# SCH_fateh_reverse_voltage_protection_cir.net
KiCad netlist of a schematic drawn in EasyEDA
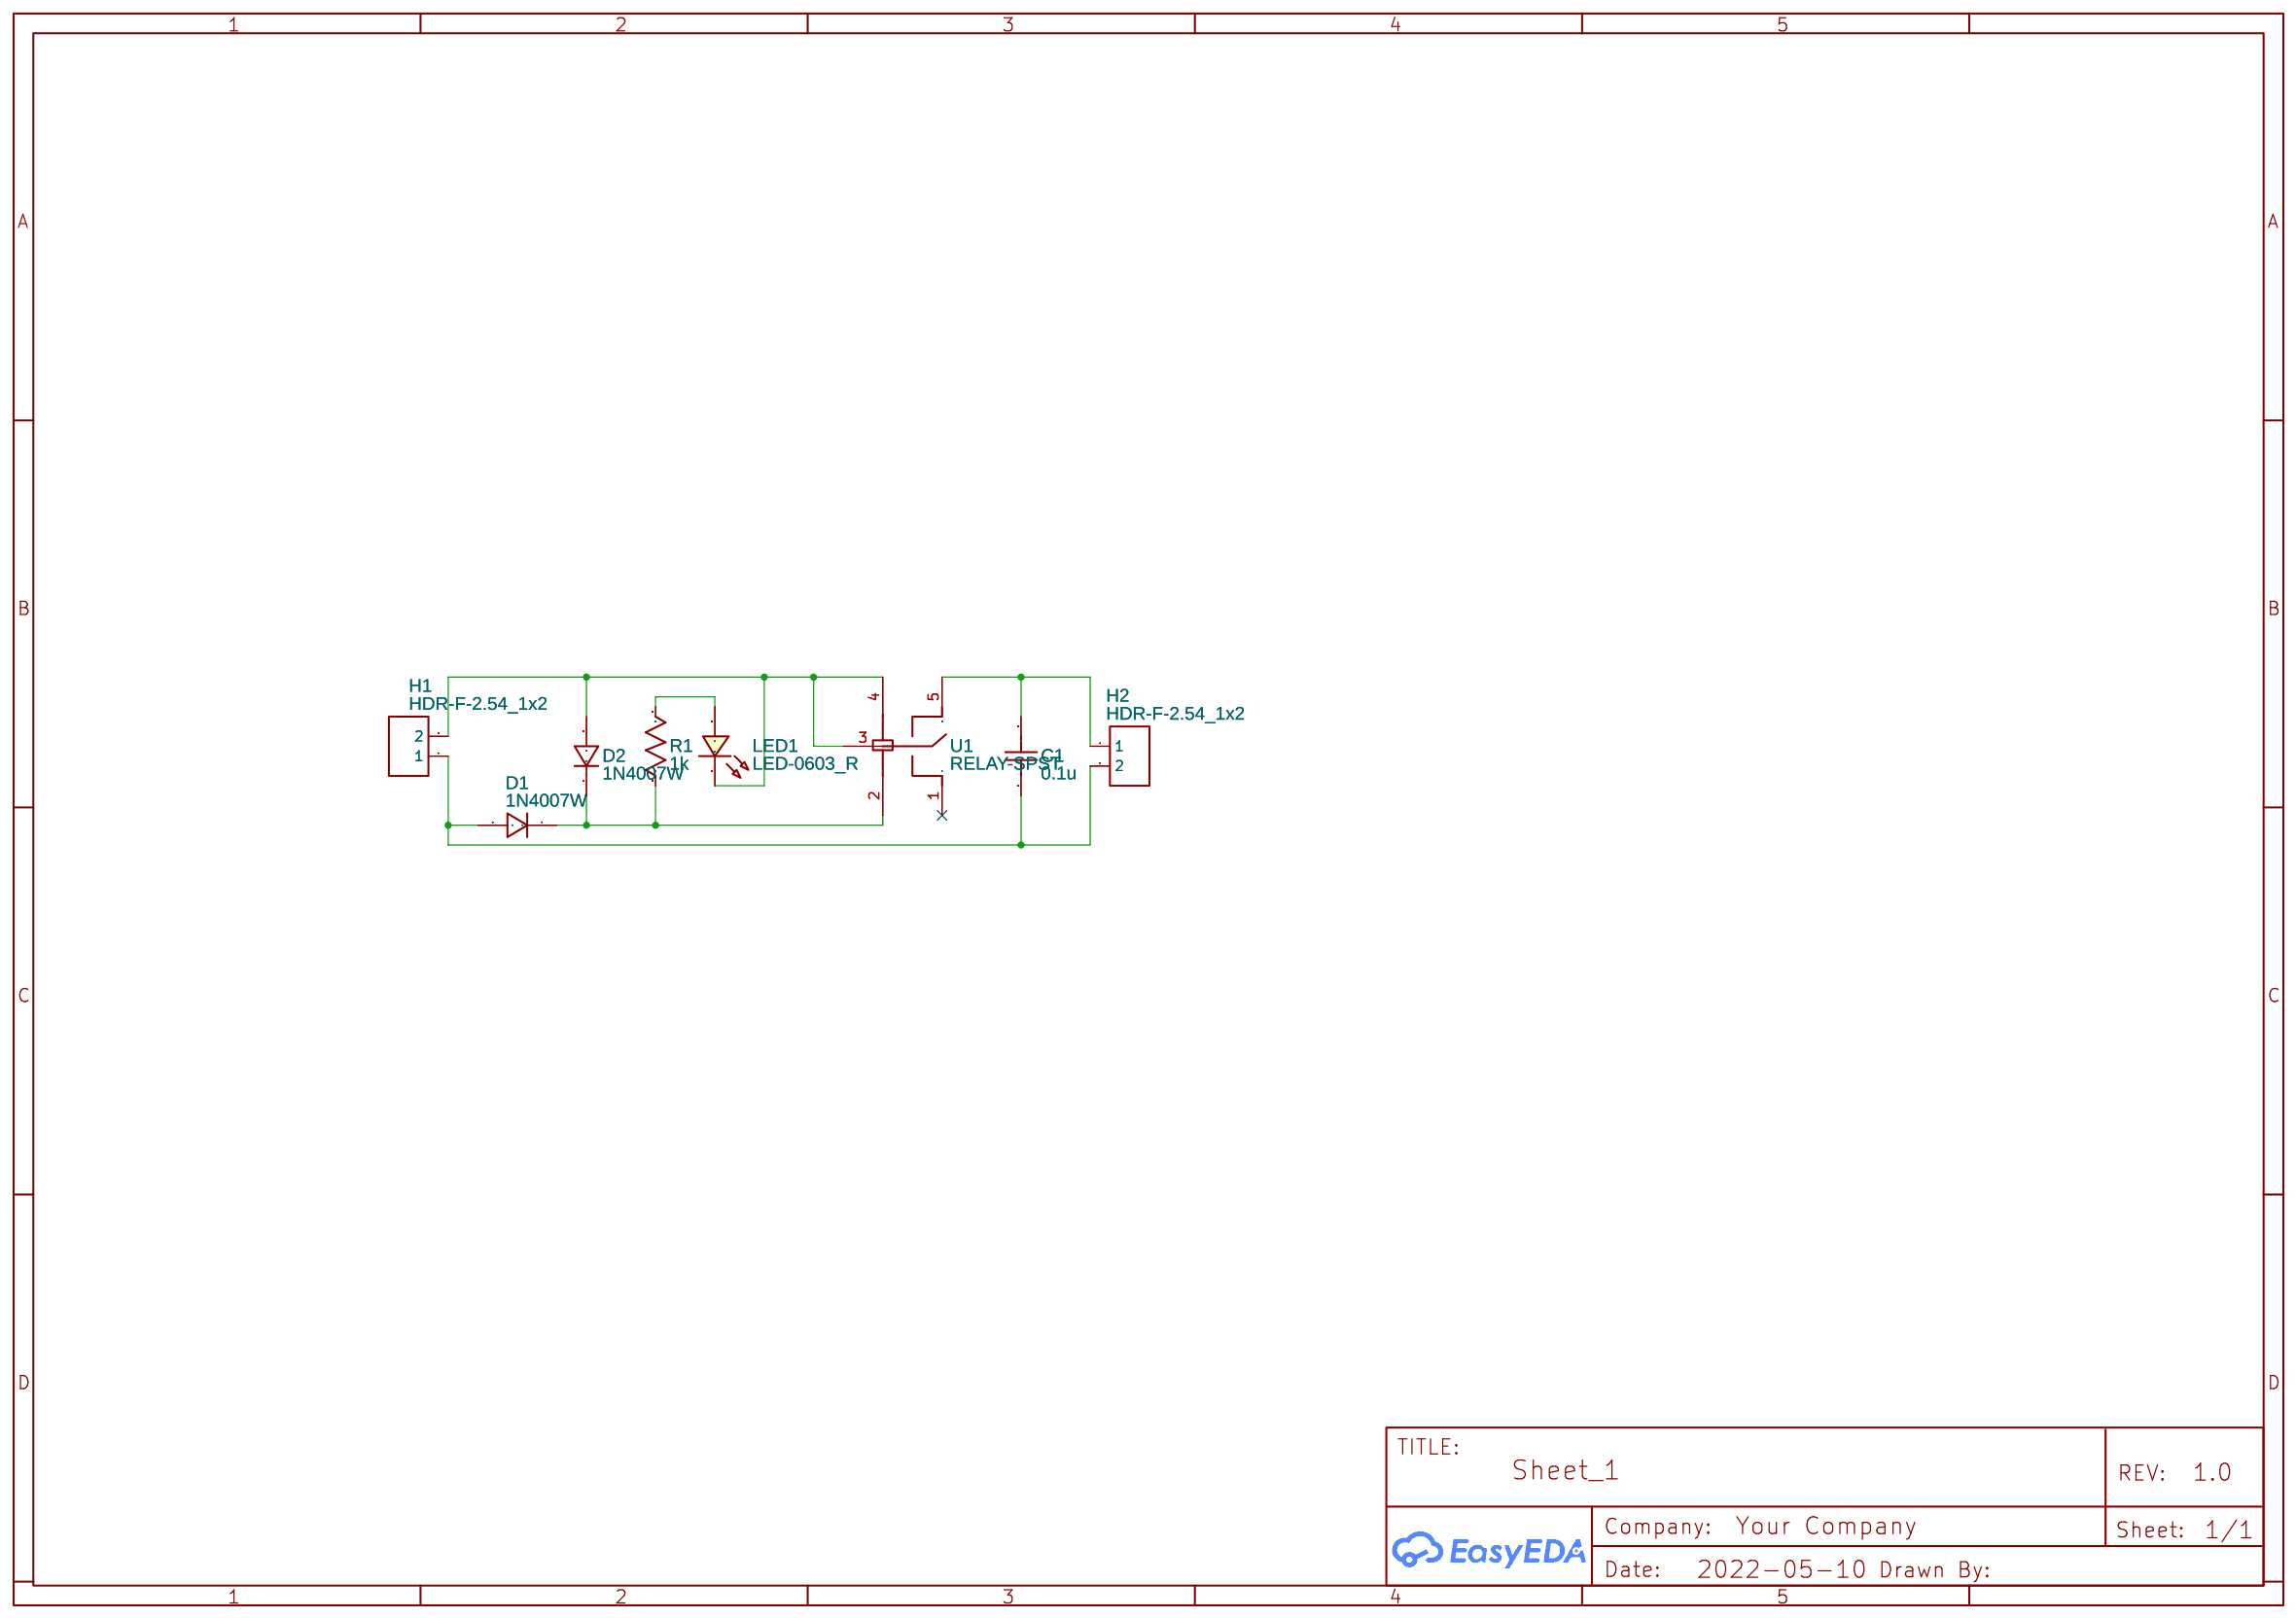
[diagram p0: schematic sheet]

(export (version "E")
  (design (tool "Eeschema 10.0.6"))
  (components
    (comp (ref "C1") (value "0.1u") (libsource (lib "") (part "C_0603_US")))
    (comp (ref "D1")
      (value "1N4007W")
      (fields (field (name "BOM_Supplier Part") "C328592"))
      (libsource (lib "") (part "1N4007W_1"))
    )
    (comp (ref "D2")
      (value "1N4007W")
      (fields (field (name "BOM_Supplier Part") "C328592"))
      (libsource (lib "") (part "1N4007W"))
    )
    (comp (ref "H1")
      (value "HDR-F-2.54_1x2")
      (fields (field (name "BOM_Supplier Part") "C49661"))
      (libsource (lib "") (part "HDR-F-2.54_1x2_1"))
    )
    (comp (ref "H2")
      (value "HDR-F-2.54_1x2")
      (fields (field (name "BOM_Supplier Part") "C49661"))
      (libsource (lib "") (part "HDR-F-2.54_1x2"))
    )
    (comp (ref "LED1")
      (value "LED-0603_R")
      (fields
        (field (name "BOM_Manufacturer Part") "19-217/R6C-AL1M2VY/3T")
        (field (name "BOM_Supplier Part") "C72044")
      )
      (libsource (lib "") (part "LED-0603_R"))
    )
    (comp (ref "R1") (value "1k") (libsource (lib "") (part "R_AXIAL-0.3_US")))
    (comp (ref "U1")
      (value "RELAY-SPST")
      (fields
        (field (name "BOM_Manufacturer Part") "Relay-SPST")
        (field (name "BOM_Supplier Part") "C2941249")
      )
      (libsource (lib "") (part "RELAY-SPST"))
    )
  )
  (nets
    (net (code "1") (name "Net-(C1-Pad1)") (class "Default")
      (node (ref "C1") (pin "1") (pinfunction "1_1") (pintype "unspecified"))
      (node (ref "D1") (pin "2") (pinfunction "2_2") (pintype "unspecified"))
      (node (ref "H1") (pin "1") (pinfunction "1_1") (pintype "input"))
      (node (ref "H2") (pin "2") (pinfunction "2_2") (pintype "input"))
    )
    (net (code "2") (name "Net-(C1-Pad2)") (class "Default")
      (node (ref "C1") (pin "2") (pinfunction "2_2") (pintype "unspecified"))
      (node (ref "H2") (pin "1") (pinfunction "1_1") (pintype "input"))
      (node (ref "U1") (pin "5") (pinfunction "5_5") (pintype "unspecified"))
    )
    (net (code "3") (name "Net-(D1-Pad1)") (class "Default")
      (node (ref "D1") (pin "1") (pinfunction "1_1") (pintype "unspecified"))
      (node (ref "D2") (pin "1") (pinfunction "1_1") (pintype "unspecified"))
      (node (ref "R1") (pin "2") (pinfunction "2_2") (pintype "unspecified"))
      (node (ref "U1") (pin "2") (pinfunction "2_2") (pintype "unspecified"))
    )
    (net (code "4") (name "Net-(D2-Pad2)") (class "Default")
      (node (ref "D2") (pin "2") (pinfunction "2_2") (pintype "unspecified"))
      (node (ref "H1") (pin "2") (pinfunction "2_2") (pintype "input"))
      (node (ref "LED1") (pin "2") (pinfunction "2_2") (pintype "unspecified"))
      (node (ref "U1") (pin "3") (pinfunction "3_3") (pintype "unspecified"))
      (node (ref "U1") (pin "4") (pinfunction "4_4") (pintype "unspecified"))
    )
    (net (code "5") (name "Net-(LED1-Pad1)") (class "Default")
      (node (ref "LED1") (pin "1") (pinfunction "1_1") (pintype "unspecified"))
      (node (ref "R1") (pin "1") (pinfunction "1_1") (pintype "unspecified"))
    )
    (net (code "6") (name "unconnected-(U1-Pad1)") (class "Default")
      (node (ref "U1") (pin "1") (pinfunction "1_1") (pintype "unspecified+no_connect"))
    )
  )
)
